# InputOutput.net
KiCad netlist of a schematic drawn in Altium Designer
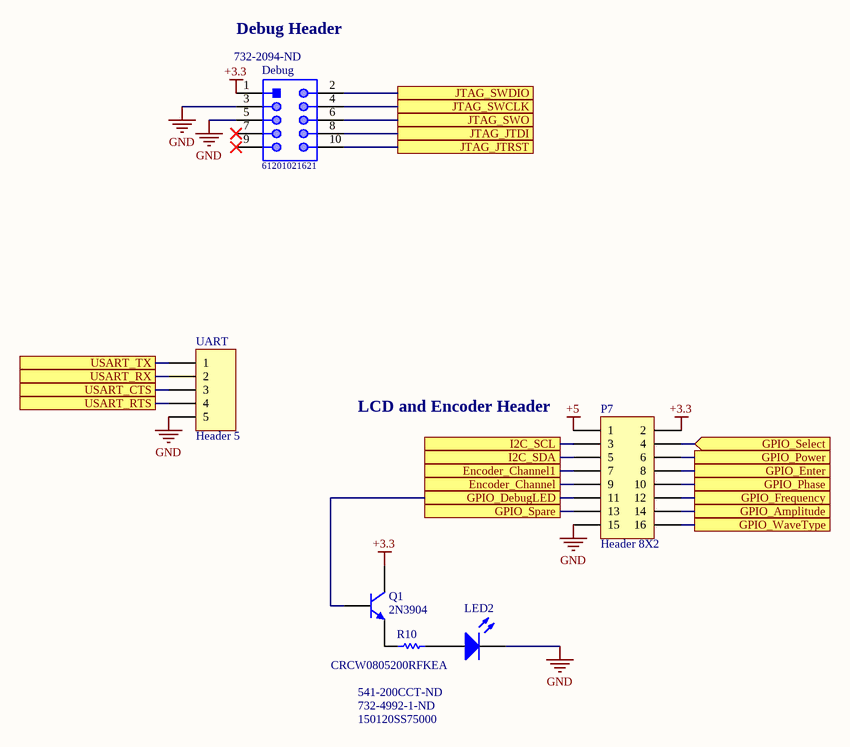
[diagram p0: InputOutput.SchDoc]

(export (version "E")
  (design (tool "Eeschema 10.0.6"))
  (components
    (comp (ref "Debug")
      (value "61201021621")
      (footprint "61201021621")
      (description "Male Box Header WR-BHD, THT, Vertical, pitch 2.54 mm, 10 pins")
      (fields
        (field (name "MANUFACTURER") "Wurth Elektronik")
        (field (name "SUPPLIER PART NUMBER 1") "732-2094-ND")
        (field (name "PUBLISHER") "WurthElektronik")
      )
      (libsource (lib "Altium Content Vault") (part "WE-CN-2P-M-R10"))
    )
    (comp (ref "LED2")
      (value "150120SS75000")
      (footprint "1206_A")
      (description "SMD mono-color Chip LED, WL-SMCW, Super Red")
      (fields
        (field (name "MANUFACTURER") "Wuerth Elektronik")
        (field (name "SUPPLIER PART NUMBER 1") "732-4992-1-ND")
      )
      (libsource (lib "Altium Content Vault") (part "WE-LED_K1A2-2"))
    )
    (comp (ref "P7")
      (value "Header 8X2")
      (footprint "HDR2X8")
      (description "Header, 8-Pin, Dual row")
      (fields (field (name "PUBLISHER") "Altium Limited"))
      (libsource (lib "Miscellaneous Connectors") (part "Header 8X2"))
    )
    (comp (ref "Q1")
      (value "2N3904")
      (footprint "TO-92A")
      (description "NPN General Purpose Amplifier")
      (fields (field (name "PUBLISHER") "Altium Limited"))
      (libsource (lib "Miscellaneous Devices") (part "2N3904"))
    )
    (comp (ref "R10")
      (value "CRCW0805200RFKEA")
      (footprint "RESC2013X50X30NL20T20")
      (fields
        (field (name "MANUFACTURER") "Vishay Dale")
        (field (name "SUPPLIER PART NUMBER 1") "541-200CCT-ND")
        (field (name "TOLERANCE") "1%")
      )
      (libsource (lib "Altium Content Vault") (part "RES"))
    )
    (comp (ref "UART")
      (value "Header 5")
      (footprint "HDR1X5")
      (description "Header, 5-Pin")
      (fields (field (name "PUBLISHER") "Altium Limited"))
      (libsource (lib "Miscellaneous Connectors") (part "Header 5"))
    )
  )
  (nets
    (net (code "1") (name "+3.3") (class "Default")
      (node (ref "Debug") (pin "1") (pinfunction "1_1") (pintype "passive"))
      (node (ref "P7") (pin "2") (pinfunction "2_2") (pintype "passive"))
      (node (ref "Q1") (pin "3") (pinfunction "C_3") (pintype "passive"))
    )
    (net (code "2") (name "+5") (class "Default")
      (node (ref "P7") (pin "1") (pinfunction "1_1") (pintype "passive"))
    )
    (net (code "3") (name "/Encoder_Channel") (class "Default")
      (node (ref "P7") (pin "9") (pinfunction "9_9") (pintype "passive"))
    )
    (net (code "4") (name "/Encoder_Channel1") (class "Default")
      (node (ref "P7") (pin "7") (pinfunction "7_7") (pintype "passive"))
    )
    (net (code "5") (name "/GPIO_Amplitude") (class "Default")
      (node (ref "P7") (pin "14") (pinfunction "14_14") (pintype "passive"))
    )
    (net (code "6") (name "/GPIO_DebugLED") (class "Default")
      (node (ref "P7") (pin "11") (pinfunction "11_11") (pintype "passive"))
      (node (ref "Q1") (pin "2") (pinfunction "B_2") (pintype "passive"))
    )
    (net (code "7") (name "/GPIO_Enter") (class "Default")
      (node (ref "P7") (pin "8") (pinfunction "8_8") (pintype "passive"))
    )
    (net (code "8") (name "/GPIO_Frequency") (class "Default")
      (node (ref "P7") (pin "12") (pinfunction "12_12") (pintype "passive"))
    )
    (net (code "9") (name "/GPIO_Phase") (class "Default")
      (node (ref "P7") (pin "10") (pinfunction "10_10") (pintype "passive"))
    )
    (net (code "10") (name "/GPIO_Power") (class "Default")
      (node (ref "P7") (pin "6") (pinfunction "6_6") (pintype "passive"))
    )
    (net (code "11") (name "/GPIO_Select") (class "Default")
      (node (ref "P7") (pin "4") (pinfunction "4_4") (pintype "passive"))
    )
    (net (code "12") (name "/GPIO_Spare") (class "Default")
      (node (ref "P7") (pin "13") (pinfunction "13_13") (pintype "passive"))
    )
    (net (code "13") (name "/GPIO_WaveType") (class "Default")
      (node (ref "P7") (pin "16") (pinfunction "16_16") (pintype "passive"))
    )
    (net (code "14") (name "/I2C_SCL") (class "Default")
      (node (ref "P7") (pin "3") (pinfunction "3_3") (pintype "passive"))
    )
    (net (code "15") (name "/I2C_SDA") (class "Default")
      (node (ref "P7") (pin "5") (pinfunction "5_5") (pintype "passive"))
    )
    (net (code "16") (name "/JTAG_JTDI") (class "Default")
      (node (ref "Debug") (pin "8") (pinfunction "8_8") (pintype "passive"))
    )
    (net (code "17") (name "/JTAG_JTRST") (class "Default")
      (node (ref "Debug") (pin "10") (pinfunction "10_10") (pintype "passive"))
    )
    (net (code "18") (name "/JTAG_SWCLK") (class "Default")
      (node (ref "Debug") (pin "4") (pinfunction "4_4") (pintype "passive"))
    )
    (net (code "19") (name "/JTAG_SWDIO") (class "Default")
      (node (ref "Debug") (pin "2") (pinfunction "2_2") (pintype "passive"))
    )
    (net (code "20") (name "/JTAG_SWO") (class "Default")
      (node (ref "Debug") (pin "6") (pinfunction "6_6") (pintype "passive"))
    )
    (net (code "21") (name "/USART_CTS") (class "Default")
      (node (ref "UART") (pin "3") (pinfunction "3_3") (pintype "passive"))
    )
    (net (code "22") (name "/USART_RTS") (class "Default")
      (node (ref "UART") (pin "4") (pinfunction "4_4") (pintype "passive"))
    )
    (net (code "23") (name "/USART_RX") (class "Default")
      (node (ref "UART") (pin "2") (pinfunction "2_2") (pintype "passive"))
    )
    (net (code "24") (name "/USART_TX") (class "Default")
      (node (ref "UART") (pin "1") (pinfunction "1_1") (pintype "passive"))
    )
    (net (code "25") (name "GND") (class "Default")
      (node (ref "Debug") (pin "3") (pinfunction "3_3") (pintype "passive"))
      (node (ref "Debug") (pin "5") (pinfunction "5_5") (pintype "passive"))
      (node (ref "LED2") (pin "1") (pinfunction "K_1") (pintype "passive"))
      (node (ref "P7") (pin "15") (pinfunction "15_15") (pintype "passive"))
      (node (ref "UART") (pin "5") (pinfunction "5_5") (pintype "passive"))
    )
    (net (code "26") (name "Net-(LED2-A)") (class "Default")
      (node (ref "LED2") (pin "2") (pinfunction "A_2") (pintype "passive"))
      (node (ref "R10") (pin "2") (pinfunction "2_2") (pintype "passive"))
    )
    (net (code "27") (name "Net-(Q1-E)") (class "Default")
      (node (ref "Q1") (pin "1") (pinfunction "E_1") (pintype "passive"))
      (node (ref "R10") (pin "1") (pinfunction "1_1") (pintype "passive"))
    )
    (net (code "28") (name "unconnected-(Debug-Pad7)") (class "Default")
      (node (ref "Debug") (pin "7") (pinfunction "7_7") (pintype "passive+no_connect"))
    )
    (net (code "29") (name "unconnected-(Debug-Pad9)") (class "Default")
      (node (ref "Debug") (pin "9") (pinfunction "9_9") (pintype "passive+no_connect"))
    )
  )
)
